# PCB_temp.net
KiCad netlist of a schematic drawn in Altium Designer
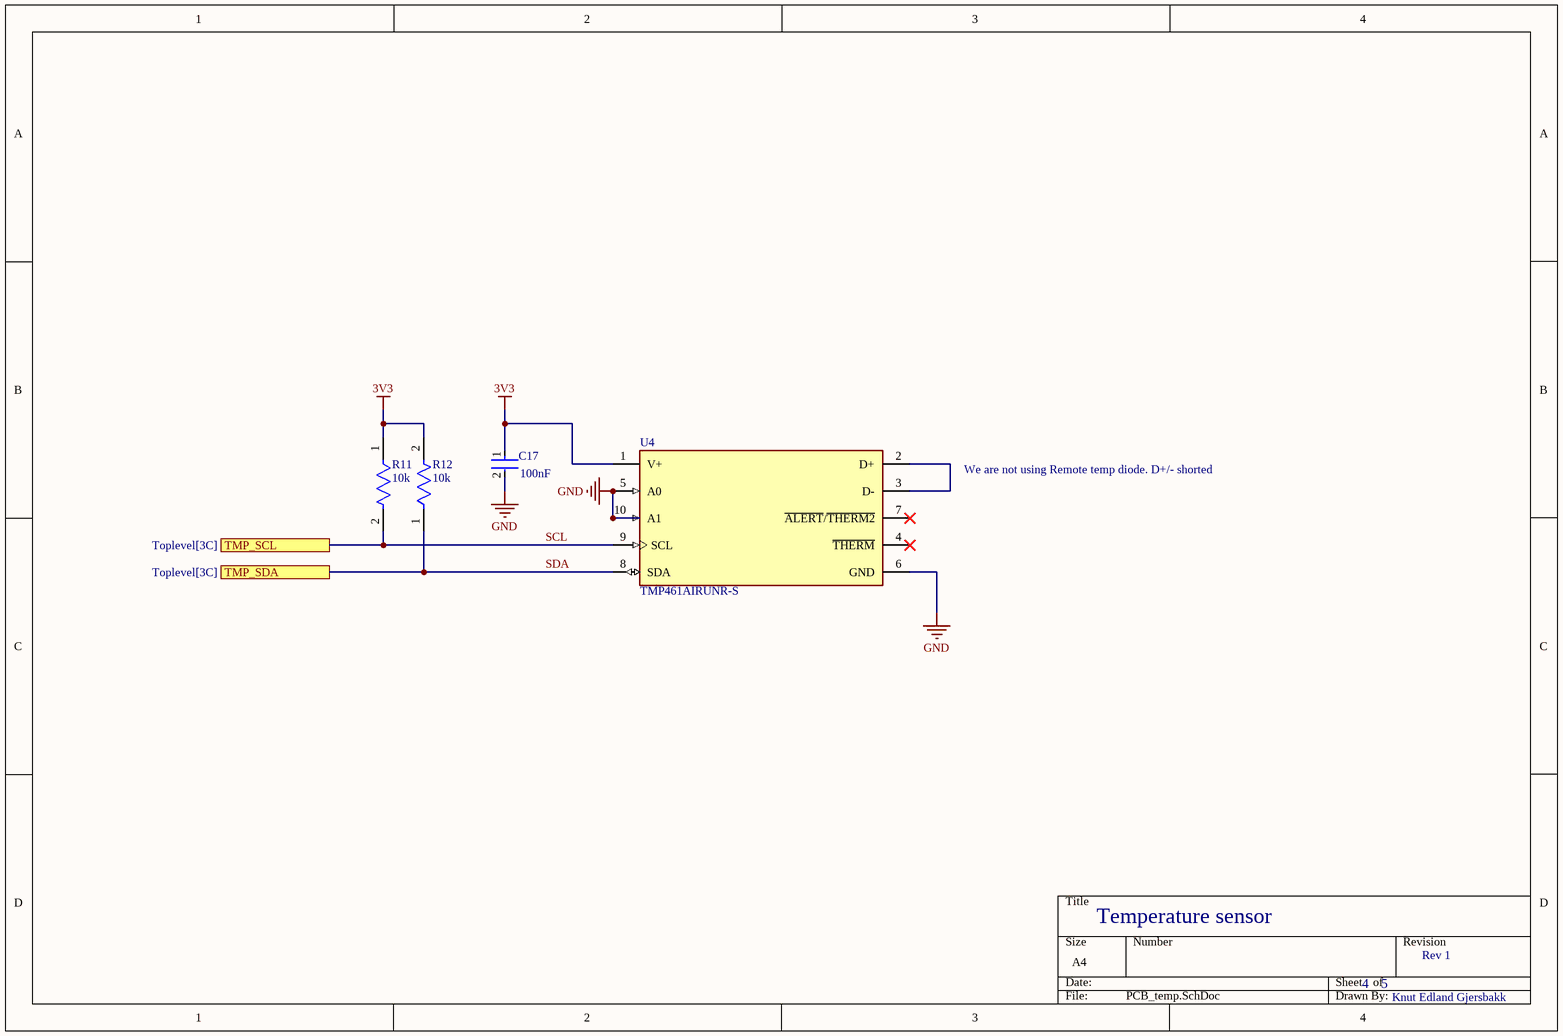
[diagram p0: PCB_temp.SchDoc]

(export (version "E")
  (design (tool "Eeschema 10.0.6"))
  (components
    (comp (ref "C17")
      (value "100nF")
      (footprint "FP-CL10-IPC_A")
      (description "Cap Ceramic 100nF 16V X7R ±10% Pad SMD 0603 +125°C T/R")
      (fields (field (name "TOLERANCE") "10%"))
      (libsource (lib "Altium Content Vault") (part "b4654b650e69147ec39a6b967a45e02"))
    )
    (comp (ref "R11")
      (value "10k")
      (footprint "FP-RT0603-IPC_C")
      (description "RES SMD 10K OHM 1% 1/10W 0603\r\nRT0603FRE0710KL")
      (fields
        (field (name "MANUFACTURER") "Yageo")
        (field (name "OCTOPART") "https://octopart.com/rt0603fre0710kl-yageo-40009243")
      )
      (libsource (lib "Altium Content Vault") (part "1029c3af85768c4190bb7ad29bc67b5"))
    )
    (comp (ref "R12")
      (value "10k")
      (footprint "FP-RT0603-IPC_C")
      (description "RES SMD 10K OHM 1% 1/10W 0603\r\nRT0603FRE0710KL")
      (fields
        (field (name "MANUFACTURER") "Yageo")
        (field (name "OCTOPART") "https://octopart.com/rt0603fre0710kl-yageo-40009243")
      )
      (libsource (lib "Altium Content Vault") (part "1029c3af85768c4190bb7ad29bc67b5"))
    )
    (comp (ref "U4")
      (value "TMP461AIRUNR-S")
      (footprint "FP-RUN0010A-MFG")
      (description "TMP461AIRUNR-S Temperature Sensor Digital, Local/Remote -40°C ~ 125°C 11 b 10-WQFN (2x2)")
      (libsource (lib "Altium Content Vault") (part "1dbd92a773e9bf4290f1d0262c0b827"))
    )
  )
  (nets
    (net (code "1") (name "/SCL") (class "Default")
      (node (ref "R11") (pin "2") (pinfunction "2_2") (pintype "passive"))
      (node (ref "U4") (pin "9") (pinfunction "SCL_9") (pintype "input"))
    )
    (net (code "2") (name "/SDA") (class "Default")
      (node (ref "R12") (pin "1") (pinfunction "1_1") (pintype "passive"))
      (node (ref "U4") (pin "8") (pinfunction "SDA_8") (pintype "bidirectional"))
    )
    (net (code "3") (name "3V3") (class "Default")
      (node (ref "C17") (pin "1") (pinfunction "1_1") (pintype "passive"))
      (node (ref "R11") (pin "1") (pinfunction "1_1") (pintype "passive"))
      (node (ref "R12") (pin "2") (pinfunction "2_2") (pintype "passive"))
      (node (ref "U4") (pin "1") (pinfunction "V+_1") (pintype "power_in"))
    )
    (net (code "4") (name "GND") (class "Default")
      (node (ref "C17") (pin "2") (pinfunction "2_2") (pintype "passive"))
      (node (ref "U4") (pin "10") (pinfunction "A1_10") (pintype "input"))
      (node (ref "U4") (pin "5") (pinfunction "A0_5") (pintype "input"))
      (node (ref "U4") (pin "6") (pinfunction "GND_6") (pintype "power_in"))
    )
    (net (code "5") (name "Net-(U4-D+)") (class "Default")
      (node (ref "U4") (pin "2") (pinfunction "D+_2") (pintype "passive"))
      (node (ref "U4") (pin "3") (pinfunction "D-_3") (pintype "passive"))
    )
    (net (code "6") (name "unconnected-(U4-~{ALERT}{slash}~{THERM2}-Pad7)") (class "Default")
      (node (ref "U4") (pin "7") (pinfunction "~{ALERT}/~{THERM2}_7") (pintype "open_collector+no_connect"))
    )
    (net (code "7") (name "unconnected-(U4-~{THERM}-Pad4)") (class "Default")
      (node (ref "U4") (pin "4") (pinfunction "~{THERM}_4") (pintype "open_collector+no_connect"))
    )
  )
)
